# internalhookup.net
KiCad netlist of a schematic drawn in EAGLE
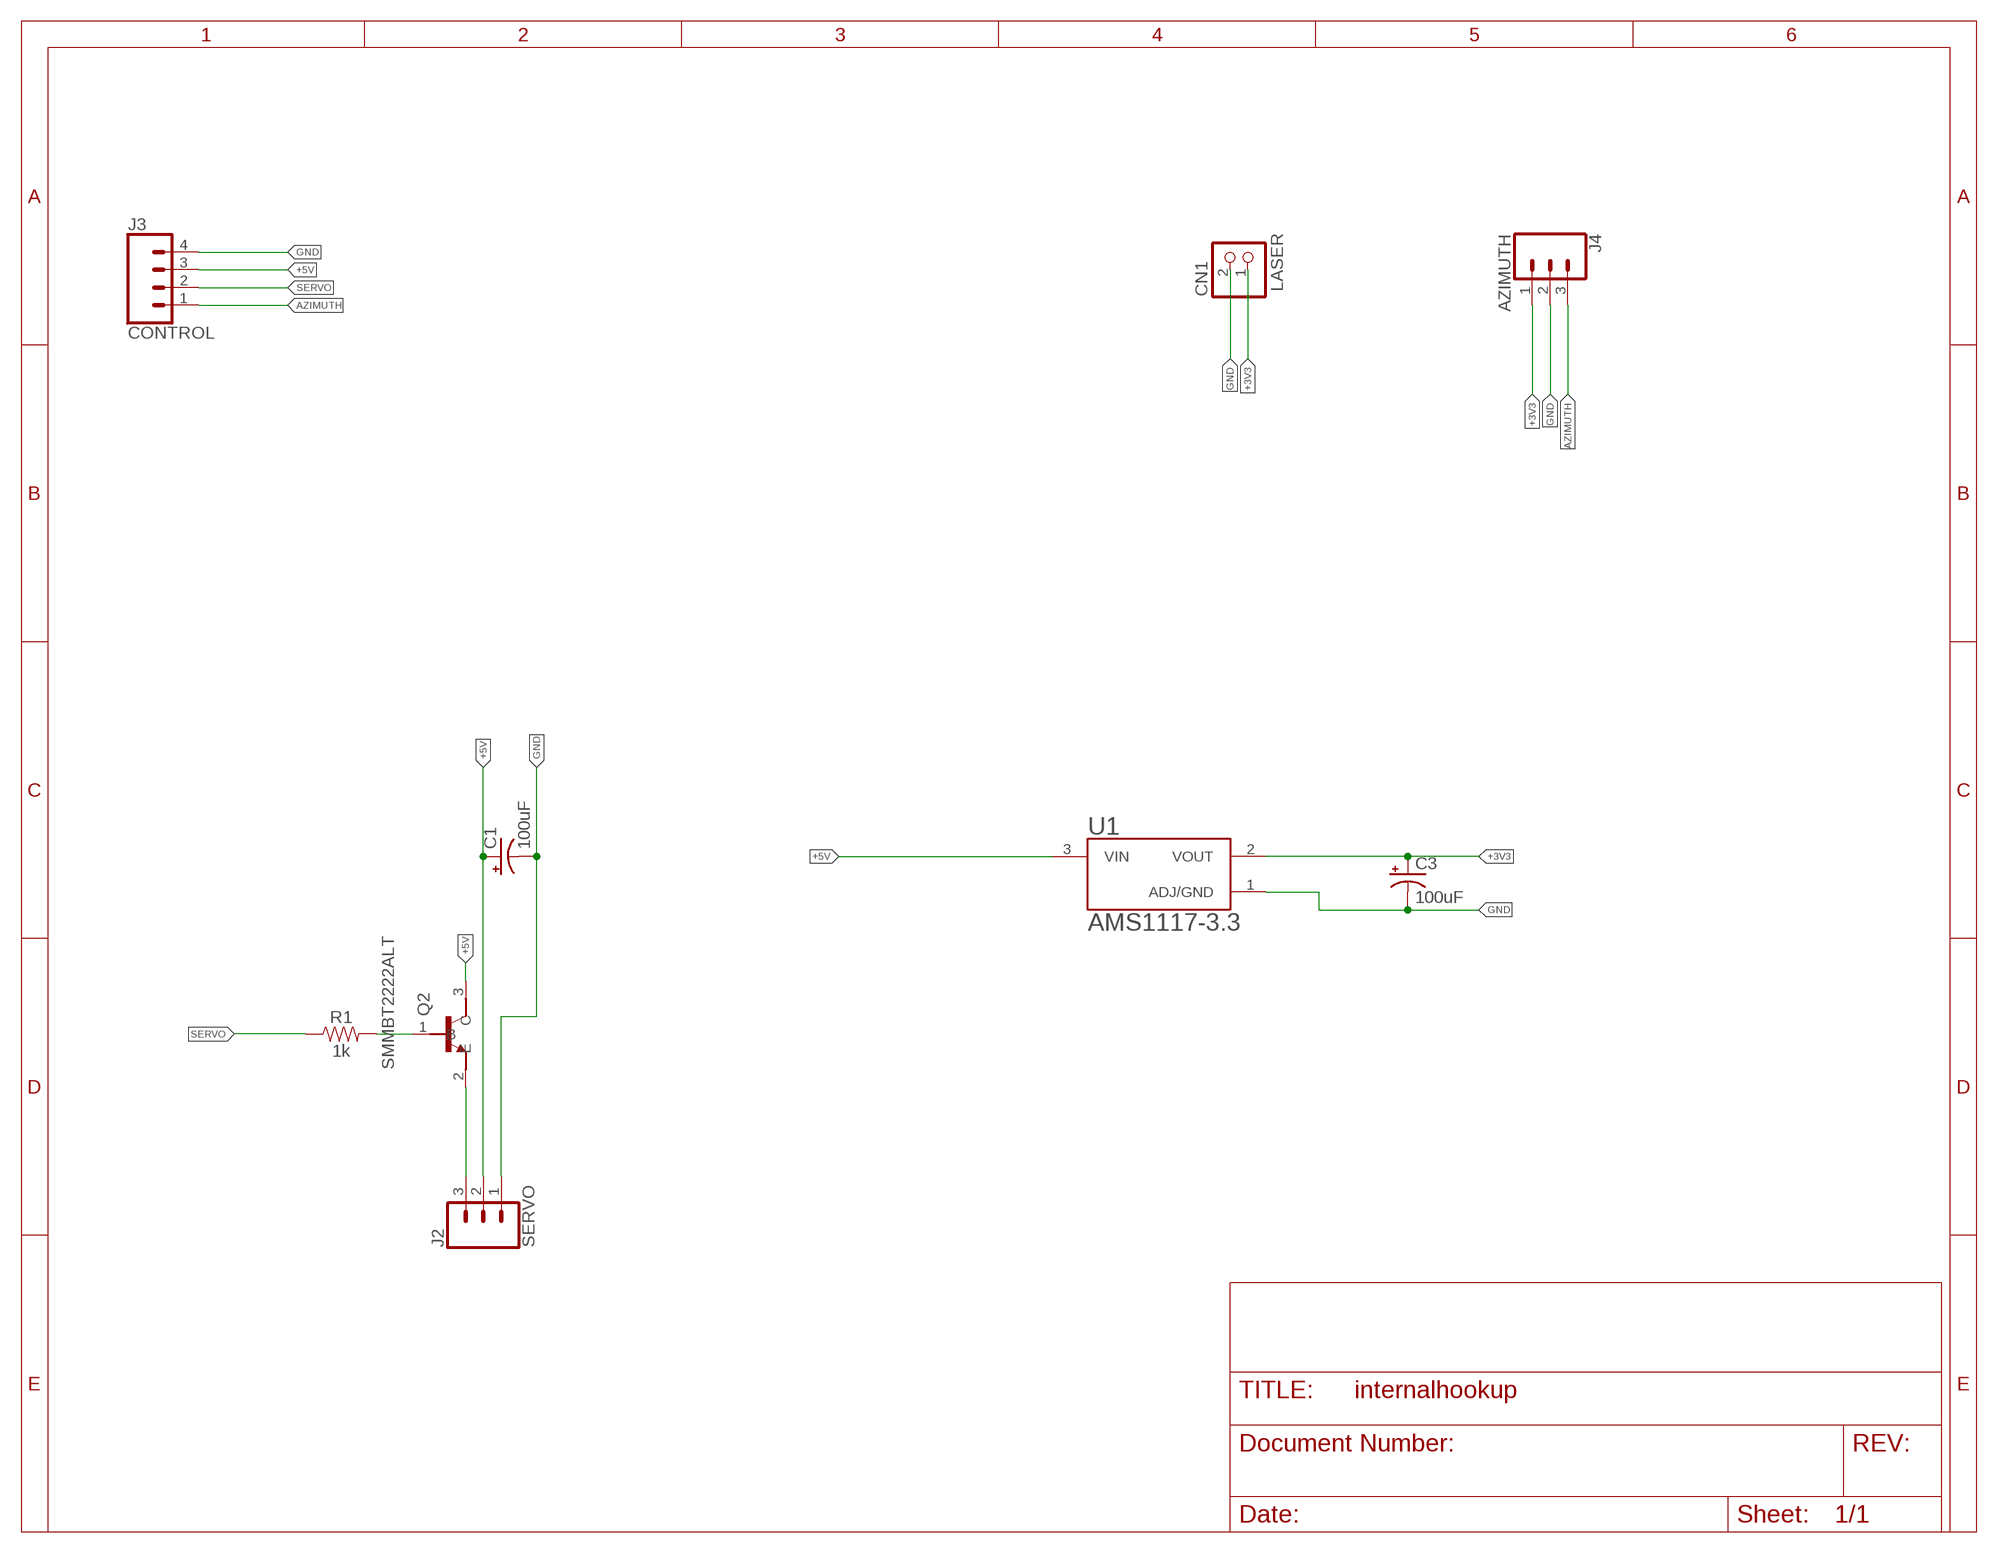
[diagram p0: schematic, sheet 1]

(export (version "E")
  (design (tool "Eeschema 10.0.6"))
  (components
    (comp (ref "C1")
      (value "100uF")
      (footprint "eagle-import:CPOL-RADIAL-2.5MM-6.5MM")
      (libsource (lib "eagle-import") (part "100UF-POLAR-RADIAL-2.5MM-25V-20%"))
    )
    (comp (ref "C3")
      (value "100uF")
      (footprint "eagle-import:CPOL-RADIAL-2.5MM-6.5MM")
      (libsource (lib "eagle-import") (part "100UF-POLAR-RADIAL-2.5MM-25V-20%"))
    )
    (comp (ref "CN1")
      (value "LASER")
      (footprint "eagle-import:JST-PH-2-THM-RA")
      (libsource (lib "eagle-import") (part "JST_2PIN-THM-RA"))
    )
    (comp (ref "J2")
      (value "SERVO")
      (footprint "eagle-import:1X03")
      (libsource (lib "eagle-import") (part "CONN_03"))
    )
    (comp (ref "J3")
      (value "CONTROL")
      (footprint "eagle-import:1X04")
      (libsource (lib "eagle-import") (part "CONN_04"))
    )
    (comp (ref "J4")
      (value "AZIMUTH")
      (footprint "eagle-import:1X03")
      (libsource (lib "eagle-import") (part "CONN_03"))
    )
    (comp (ref "Q2")
      (value "SMMBT2222ALT")
      (footprint "eagle-import:SOT95P240X120-3N")
      (fields (field (name "MF") "STMicroelectronics") (field (name "MP") "MMBT3904"))
      (libsource (lib "eagle-import") (part "MMBT3904"))
    )
    (comp (ref "R1")
      (value "1k")
      (footprint "eagle-import:0805")
      (libsource (lib "eagle-import") (part "0.3OHM-0805-1/8W-1%"))
    )
    (comp (ref "U1")
      (value "AMS1117-3.3")
      (footprint "eagle-import:SOT229P700X180-4N")
      (fields (field (name "MF") "Advanced Monolithic Systems"))
      (libsource (lib "eagle-import") (part "AMS1117-3.3"))
    )
  )
  (nets
    (net (code "1") (name "+3V3") (class "Default")
      (node (ref "C3") (pin "1") (pinfunction "+_1") (pintype "passive"))
      (node (ref "CN1") (pin "1") (pinfunction "2_1") (pintype "passive"))
      (node (ref "J4") (pin "1") (pinfunction "1_1") (pintype "passive"))
      (node (ref "U1") (pin "2") (pinfunction "VOUT_2") (pintype "output"))
    )
    (net (code "2") (name "+5V") (class "Default")
      (node (ref "C1") (pin "1") (pinfunction "+_1") (pintype "passive"))
      (node (ref "J2") (pin "2") (pinfunction "2_2") (pintype "passive"))
      (node (ref "J3") (pin "3") (pinfunction "3_3") (pintype "passive"))
      (node (ref "Q2") (pin "3") (pinfunction "C_3") (pintype "passive"))
      (node (ref "U1") (pin "3") (pinfunction "VIN_3") (pintype "input"))
    )
    (net (code "3") (name "AZIMUTH") (class "Default")
      (node (ref "J3") (pin "1") (pinfunction "1_1") (pintype "passive"))
      (node (ref "J4") (pin "3") (pinfunction "3_3") (pintype "passive"))
    )
    (net (code "4") (name "GND") (class "Default")
      (node (ref "C1") (pin "2") (pinfunction "-_2") (pintype "passive"))
      (node (ref "C3") (pin "2") (pinfunction "-_2") (pintype "passive"))
      (node (ref "CN1") (pin "2") (pinfunction "1_2") (pintype "passive"))
      (node (ref "J2") (pin "1") (pinfunction "1_1") (pintype "passive"))
      (node (ref "J3") (pin "4") (pinfunction "4_4") (pintype "passive"))
      (node (ref "J4") (pin "2") (pinfunction "2_2") (pintype "passive"))
      (node (ref "U1") (pin "1") (pinfunction "ADJ/GND_1") (pintype "power_in"))
    )
    (net (code "5") (name "Net-(Q2-B)") (class "Default")
      (node (ref "Q2") (pin "1") (pinfunction "B_1") (pintype "passive"))
      (node (ref "R1") (pin "2") (pinfunction "2_2") (pintype "passive"))
    )
    (net (code "6") (name "Net-(Q2-E)") (class "Default")
      (node (ref "J2") (pin "3") (pinfunction "3_3") (pintype "passive"))
      (node (ref "Q2") (pin "2") (pinfunction "E_2") (pintype "passive"))
    )
    (net (code "7") (name "SERVO") (class "Default")
      (node (ref "J3") (pin "2") (pinfunction "2_2") (pintype "passive"))
      (node (ref "R1") (pin "1") (pinfunction "1_1") (pintype "passive"))
    )
  )
)
